# heart_eyes_gold.net
KiCad netlist of a schematic drawn in EAGLE
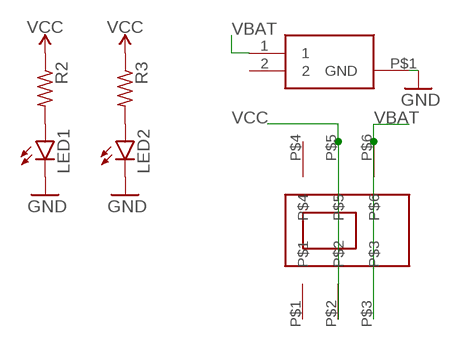
[diagram p0: schematic, sheet 1]

(export (version "E")
  (design (tool "Eeschema 10.0.6"))
  (components
    (comp (ref "LED1")
      (value "LEDCHIP-LED0805")
      (footprint "eagle-import:CHIP-LED0805")
      (libsource (lib "eagle-import") (part "LEDCHIP-LED0805"))
    )
    (comp (ref "LED2")
      (value "LEDCHIP-LED0805")
      (footprint "eagle-import:CHIP-LED0805")
      (libsource (lib "eagle-import") (part "LEDCHIP-LED0805"))
    )
    (comp (ref "R2")
      (value "R-US_R0603")
      (footprint "eagle-import:R0603")
      (libsource (lib "eagle-import") (part "R-US_R0603"))
    )
    (comp (ref "R3")
      (value "R-US_R0603")
      (footprint "eagle-import:R0603")
      (libsource (lib "eagle-import") (part "R-US_R0603"))
    )
    (comp (ref "U$1")
      (value "CL-SB-22A-02T-SLIDE-SWITCH-TUCKED-PADS")
      (footprint "eagle-import:CL-SB-22A-02T-DPDT-COMPACT-SWITCH")
      (libsource (lib "eagle-import") (part "CL-SB-22A-02T-SLIDE-SWITCH-TUCKED-PADS"))
    )
    (comp (ref "VBAT")
      (value "BAT-HLD-012-SMT")
      (footprint "eagle-import:BATHLD012SMT")
      (fields (field (name "MOUSER_PART_NUMBER") "712-BAT-HLD-012-SMT"))
      (libsource (lib "eagle-import") (part "BAT-HLD-012-SMT"))
    )
  )
  (nets
    (net (code "1") (name "/VBAT") (class "Default")
      (node (ref "U$1") (pin "P$3") (pinfunction "P$3_P$3") (pintype "bidirectional"))
      (node (ref "U$1") (pin "P$6") (pinfunction "P$6_P$6") (pintype "bidirectional"))
      (node (ref "VBAT") (pin "1") (pinfunction "1_1") (pintype "bidirectional"))
    )
    (net (code "2") (name "GND") (class "Default")
      (node (ref "LED1") (pin "C") (pinfunction "C_C") (pintype "passive"))
      (node (ref "LED2") (pin "C") (pinfunction "C_C") (pintype "passive"))
      (node (ref "VBAT") (pin "P$1") (pinfunction "GND_P$1") (pintype "bidirectional"))
    )
    (net (code "3") (name "Net-(LED1-PadA)") (class "Default")
      (node (ref "LED1") (pin "A") (pinfunction "A_A") (pintype "passive"))
      (node (ref "R2") (pin "2") (pinfunction "2_2") (pintype "passive"))
    )
    (net (code "4") (name "Net-(LED2-PadA)") (class "Default")
      (node (ref "LED2") (pin "A") (pinfunction "A_A") (pintype "passive"))
      (node (ref "R3") (pin "2") (pinfunction "2_2") (pintype "passive"))
    )
    (net (code "5") (name "VCC") (class "Default")
      (node (ref "R2") (pin "1") (pinfunction "1_1") (pintype "passive"))
      (node (ref "R3") (pin "1") (pinfunction "1_1") (pintype "passive"))
      (node (ref "U$1") (pin "P$2") (pinfunction "P$2_P$2") (pintype "bidirectional"))
      (node (ref "U$1") (pin "P$5") (pinfunction "P$5_P$5") (pintype "bidirectional"))
    )
    (net (code "6") (name "unconnected-(U$1-PadP$1)") (class "Default")
      (node (ref "U$1") (pin "P$1") (pinfunction "P$1_P$1") (pintype "bidirectional"))
    )
    (net (code "7") (name "unconnected-(U$1-PadP$4)") (class "Default")
      (node (ref "U$1") (pin "P$4") (pinfunction "P$4_P$4") (pintype "bidirectional"))
    )
    (net (code "8") (name "unconnected-(VBAT-Pad2)") (class "Default")
      (node (ref "VBAT") (pin "2") (pinfunction "2_2") (pintype "bidirectional"))
    )
  )
)
